# Un_Arduino.net
KiCad netlist of a schematic drawn in EAGLE
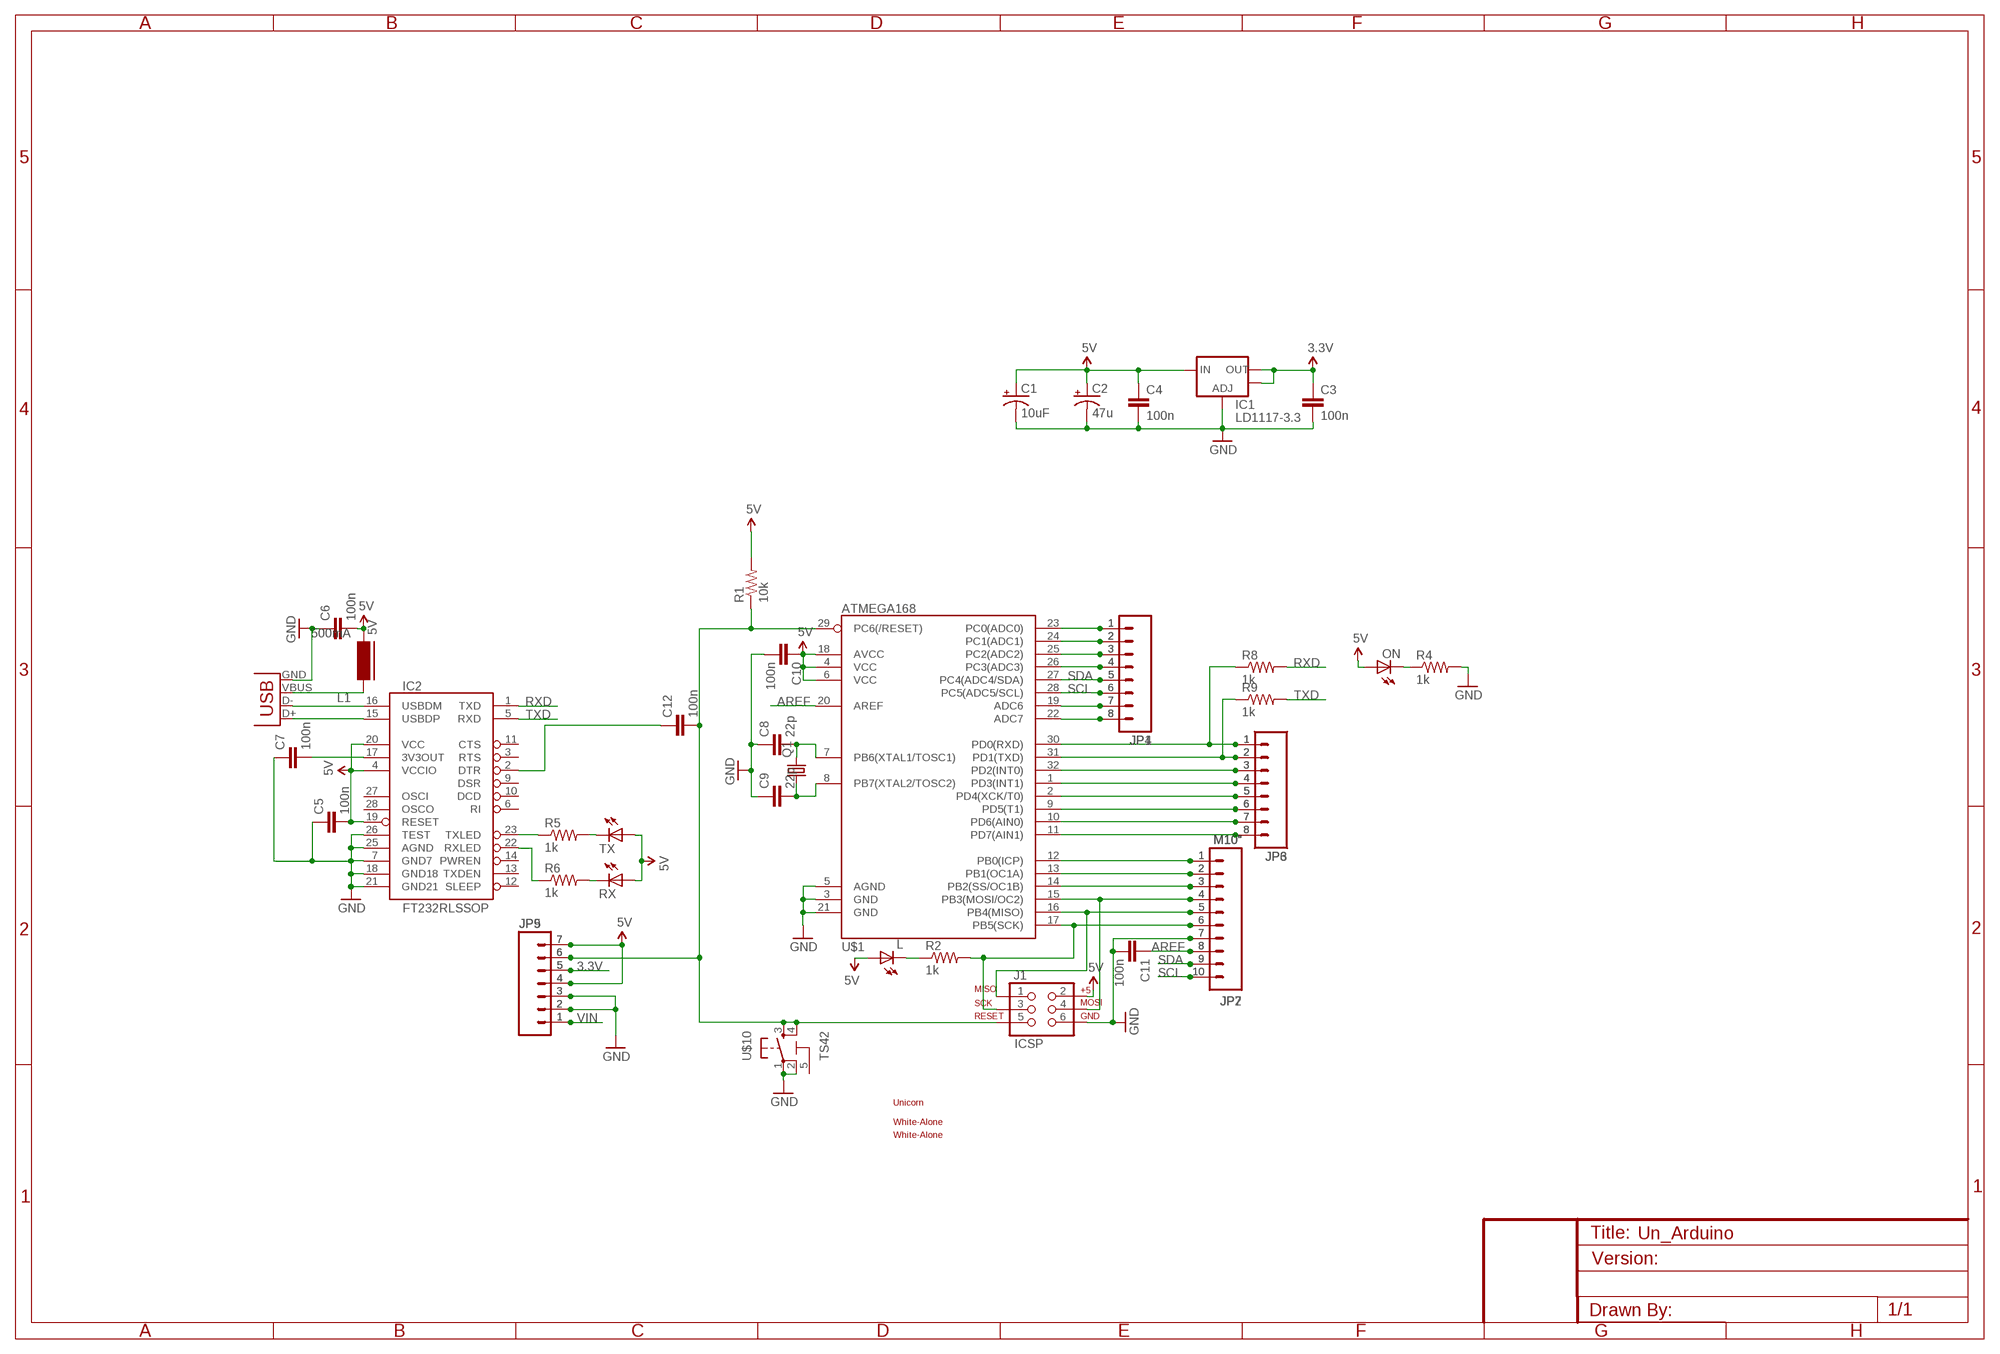
[diagram p0: schematic, sheet 1]

(export (version "E")
  (design (tool "Eeschema 10.0.6"))
  (components
    (comp (ref "C1")
      (value "10uF")
      (footprint "eagle-import:EIA3216")
      (libsource (lib "eagle-import") (part "CAP_POL1206"))
    )
    (comp (ref "C2")
      (value "47u")
      (footprint "eagle-import:PANASONIC_D")
      (libsource (lib "eagle-import") (part "CAP_POLD"))
    )
    (comp (ref "C3")
      (value "100n")
      (footprint "eagle-import:0603-CAP")
      (libsource (lib "eagle-import") (part "2SparkFun_CAP0603-CAP"))
    )
    (comp (ref "C4")
      (value "100n")
      (footprint "eagle-import:0603-CAP")
      (libsource (lib "eagle-import") (part "2SparkFun_CAP0603-CAP"))
    )
    (comp (ref "C5")
      (value "100n")
      (footprint "eagle-import:0603-CAP")
      (libsource (lib "eagle-import") (part "2SparkFun_CAP0603-CAP"))
    )
    (comp (ref "C6")
      (value "100n")
      (footprint "eagle-import:0603-CAP")
      (libsource (lib "eagle-import") (part "2SparkFun_CAP0603-CAP"))
    )
    (comp (ref "C7")
      (value "100n")
      (footprint "eagle-import:0603-CAP")
      (libsource (lib "eagle-import") (part "2SparkFun_CAP0603-CAP"))
    )
    (comp (ref "C8")
      (value "22p")
      (footprint "eagle-import:0603-CAP")
      (libsource (lib "eagle-import") (part "2SparkFun_CAP0603-CAP"))
    )
    (comp (ref "C9")
      (value "22p")
      (footprint "eagle-import:0603-CAP")
      (libsource (lib "eagle-import") (part "2SparkFun_CAP0603-CAP"))
    )
    (comp (ref "C10")
      (value "100n")
      (footprint "eagle-import:0603-CAP")
      (libsource (lib "eagle-import") (part "2SparkFun_CAP0603-CAP"))
    )
    (comp (ref "C11")
      (value "100n")
      (footprint "eagle-import:0603-CAP")
      (libsource (lib "eagle-import") (part "2SparkFun_CAP0603-CAP"))
    )
    (comp (ref "C12")
      (value "100n")
      (footprint "eagle-import:0603-CAP")
      (libsource (lib "eagle-import") (part "CAP0603-CAP"))
    )
    (comp (ref "IC1")
      (value "LD1117-3.3")
      (footprint "eagle-import:SOT223")
      (libsource (lib "eagle-import") (part "V_REG_LM1117SOT223"))
    )
    (comp (ref "IC2")
      (value "FT232RLSSOP")
      (footprint "eagle-import:SSOP28DB")
      (libsource (lib "eagle-import") (part "FT232RLSSOP"))
    )
    (comp (ref "J1")
      (value "ICSP")
      (footprint "eagle-import:2X3")
      (libsource (lib "eagle-import") (part "AVR_SPI_PRG_6PTH"))
    )
    (comp (ref "JP1")
      (value "M081X08")
      (footprint "eagle-import:1X08")
      (libsource (lib "eagle-import") (part "M081X08"))
    )
    (comp (ref "JP2")
      (value "M10\"")
      (footprint "eagle-import:1X10")
      (libsource (lib "eagle-import") (part "M10{dblquote}"))
    )
    (comp (ref "JP3")
      (value "M08")
      (footprint "eagle-import:1X08")
      (libsource (lib "eagle-import") (part "M08"))
    )
    (comp (ref "JP4")
      (value "M081X08")
      (footprint "eagle-import:1X08")
      (libsource (lib "eagle-import") (part "M081X08"))
    )
    (comp (ref "JP5")
      (value "M07")
      (footprint "eagle-import:1X07")
      (libsource (lib "eagle-import") (part "M07"))
    )
    (comp (ref "JP6")
      (value "M08")
      (footprint "eagle-import:1X08")
      (libsource (lib "eagle-import") (part "M08"))
    )
    (comp (ref "JP7")
      (value "M10\"")
      (footprint "eagle-import:1X10")
      (libsource (lib "eagle-import") (part "M10{dblquote}"))
    )
    (comp (ref "JP9")
      (value "M07")
      (footprint "eagle-import:1X07")
      (libsource (lib "eagle-import") (part "M07"))
    )
    (comp (ref "L")
      (value "LED0805")
      (footprint "eagle-import:LED-0805")
      (libsource (lib "eagle-import") (part "LED0805"))
    )
    (comp (ref "L1")
      (value "500mA")
      (footprint "eagle-import:FB805")
      (libsource (lib "eagle-import") (part "FERRITE-0805"))
    )
    (comp (ref "ON")
      (value "LED0805")
      (footprint "eagle-import:LED-0805")
      (libsource (lib "eagle-import") (part "LED0805"))
    )
    (comp (ref "Q1")
      (value "CRYSTALHC49US")
      (footprint "eagle-import:HC49US")
      (libsource (lib "eagle-import") (part "CRYSTALHC49US"))
    )
    (comp (ref "R1")
      (value "10k")
      (footprint "eagle-import:0603-RES")
      (libsource (lib "eagle-import") (part "RESISTOR0603-RES"))
    )
    (comp (ref "R2")
      (value "1k")
      (footprint "eagle-import:0603-RES")
      (libsource (lib "eagle-import") (part "RESISTOR0603-RES"))
    )
    (comp (ref "R4")
      (value "1k")
      (footprint "eagle-import:0603-RES")
      (libsource (lib "eagle-import") (part "RESISTOR0603-RES"))
    )
    (comp (ref "R5")
      (value "1k")
      (footprint "eagle-import:0603-RES")
      (libsource (lib "eagle-import") (part "RESISTOR0603-RES"))
    )
    (comp (ref "R6")
      (value "1k")
      (footprint "eagle-import:0603-RES")
      (libsource (lib "eagle-import") (part "RESISTOR0603-RES"))
    )
    (comp (ref "R8")
      (value "1k")
      (footprint "eagle-import:0603-RES")
      (libsource (lib "eagle-import") (part "RESISTOR0603-RES"))
    )
    (comp (ref "R9")
      (value "1k")
      (footprint "eagle-import:0603-RES")
      (libsource (lib "eagle-import") (part "RESISTOR0603-RES"))
    )
    (comp (ref "RX")
      (value "LED0805")
      (footprint "eagle-import:LED-0805")
      (libsource (lib "eagle-import") (part "LED0805"))
    )
    (comp (ref "TX")
      (value "LED0805")
      (footprint "eagle-import:LED-0805")
      (libsource (lib "eagle-import") (part "LED0805"))
    )
    (comp (ref "U$1")
      (value "ATMEGA168")
      (footprint "eagle-import:TQFP32-08")
      (libsource (lib "eagle-import") (part "ATMEGA168"))
    )
    (comp (ref "U$4")
      (value "UNICORN")
      (footprint "eagle-import:UNICORN_1")
      (libsource (lib "eagle-import") (part "UNICORN"))
    )
    (comp (ref "U$10")
      (value "TS42")
      (footprint "eagle-import:TS42")
      (libsource (lib "eagle-import") (part "TS42"))
    )
    (comp (ref "U$13")
      (value "WHITE-ALONE_0")
      (footprint "eagle-import:WHITE-ALONE_0")
      (libsource (lib "eagle-import") (part "WHITE-ALONE_0"))
    )
    (comp (ref "U$14")
      (value "WHITE-ALONE_0")
      (footprint "eagle-import:WHITE-ALONE_0")
      (libsource (lib "eagle-import") (part "WHITE-ALONE_0"))
    )
    (comp (ref "X1")
      (value "USBSMD")
      (footprint "eagle-import:USB-MINIB")
      (libsource (lib "eagle-import") (part "USBSMD"))
    )
  )
  (nets
    (net (code "1") (name "/AREF") (class "Default")
      (node (ref "C11") (pin "1") (pinfunction "1_1") (pintype "passive"))
      (node (ref "JP2") (pin "8") (pinfunction "8_8") (pintype "passive"))
      (node (ref "JP7") (pin "8") (pinfunction "8_8") (pintype "passive"))
      (node (ref "U$1") (pin "20") (pinfunction "AREF_20") (pintype "bidirectional"))
    )
    (net (code "2") (name "/RXD") (class "Default")
      (node (ref "IC2") (pin "1") (pinfunction "TXD_1") (pintype "output"))
      (node (ref "R8") (pin "2") (pinfunction "2_2") (pintype "passive"))
    )
    (net (code "3") (name "/SCL") (class "Default")
      (node (ref "JP1") (pin "6") (pinfunction "6_6") (pintype "passive"))
      (node (ref "JP2") (pin "10") (pinfunction "10_10") (pintype "passive"))
      (node (ref "JP4") (pin "6") (pinfunction "6_6") (pintype "passive"))
      (node (ref "JP7") (pin "10") (pinfunction "10_10") (pintype "passive"))
      (node (ref "U$1") (pin "28") (pinfunction "PC5(ADC5/SCL)_28") (pintype "bidirectional"))
    )
    (net (code "4") (name "/SDA") (class "Default")
      (node (ref "JP1") (pin "5") (pinfunction "5_5") (pintype "passive"))
      (node (ref "JP2") (pin "9") (pinfunction "9_9") (pintype "passive"))
      (node (ref "JP4") (pin "5") (pinfunction "5_5") (pintype "passive"))
      (node (ref "JP7") (pin "9") (pinfunction "9_9") (pintype "passive"))
      (node (ref "U$1") (pin "27") (pinfunction "PC4(ADC4/SDA)_27") (pintype "bidirectional"))
    )
    (net (code "5") (name "/TXD") (class "Default")
      (node (ref "IC2") (pin "5") (pinfunction "RXD_5") (pintype "input"))
      (node (ref "R9") (pin "2") (pinfunction "2_2") (pintype "passive"))
    )
    (net (code "6") (name "/VIN") (class "Default")
      (node (ref "JP5") (pin "1") (pinfunction "1_1") (pintype "passive"))
      (node (ref "JP9") (pin "1") (pinfunction "1_1") (pintype "passive"))
    )
    (net (code "7") (name "3.3V") (class "Default")
      (node (ref "C3") (pin "1") (pinfunction "1_1") (pintype "passive"))
      (node (ref "IC1") (pin "2") (pinfunction "OUT_2") (pintype "output"))
      (node (ref "IC1") (pin "4") (pinfunction "OUT_4") (pintype "output"))
      (node (ref "JP5") (pin "5") (pinfunction "5_5") (pintype "passive"))
      (node (ref "JP9") (pin "5") (pinfunction "5_5") (pintype "passive"))
    )
    (net (code "8") (name "5V") (class "Default")
      (node (ref "C1") (pin "A") (pinfunction "+_A") (pintype "passive"))
      (node (ref "C10") (pin "1") (pinfunction "1_1") (pintype "passive"))
      (node (ref "C2") (pin "+") (pinfunction "+_+") (pintype "passive"))
      (node (ref "C4") (pin "1") (pinfunction "1_1") (pintype "passive"))
      (node (ref "C5") (pin "2") (pinfunction "2_2") (pintype "passive"))
      (node (ref "C6") (pin "2") (pinfunction "2_2") (pintype "passive"))
      (node (ref "IC1") (pin "3") (pinfunction "IN_3") (pintype "input"))
      (node (ref "IC2") (pin "19") (pinfunction "RESET_19") (pintype "input"))
      (node (ref "IC2") (pin "20") (pinfunction "VCC_20") (pintype "power_in"))
      (node (ref "IC2") (pin "4") (pinfunction "VCCIO_4") (pintype "power_in"))
      (node (ref "J1") (pin "2") (pinfunction "2_2") (pintype "passive"))
      (node (ref "JP5") (pin "4") (pinfunction "4_4") (pintype "passive"))
      (node (ref "JP5") (pin "7") (pinfunction "7_7") (pintype "passive"))
      (node (ref "JP9") (pin "4") (pinfunction "4_4") (pintype "passive"))
      (node (ref "JP9") (pin "7") (pinfunction "7_7") (pintype "passive"))
      (node (ref "L") (pin "1") (pinfunction "A_1") (pintype "passive"))
      (node (ref "L1") (pin "2") (pinfunction "2_2") (pintype "passive"))
      (node (ref "ON") (pin "1") (pinfunction "A_1") (pintype "passive"))
      (node (ref "R1") (pin "2") (pinfunction "2_2") (pintype "passive"))
      (node (ref "RX") (pin "1") (pinfunction "A_1") (pintype "passive"))
      (node (ref "TX") (pin "1") (pinfunction "A_1") (pintype "passive"))
      (node (ref "U$1") (pin "18") (pinfunction "AVCC_18") (pintype "bidirectional"))
      (node (ref "U$1") (pin "4") (pinfunction "VCC_4") (pintype "bidirectional"))
      (node (ref "U$1") (pin "6") (pinfunction "VCC_6") (pintype "bidirectional"))
    )
    (net (code "9") (name "GND") (class "Default")
      (node (ref "C1") (pin "C") (pinfunction "-_C") (pintype "passive"))
      (node (ref "C10") (pin "2") (pinfunction "2_2") (pintype "passive"))
      (node (ref "C11") (pin "2") (pinfunction "2_2") (pintype "passive"))
      (node (ref "C2") (pin "-") (pinfunction "-_-") (pintype "passive"))
      (node (ref "C3") (pin "2") (pinfunction "2_2") (pintype "passive"))
      (node (ref "C4") (pin "2") (pinfunction "2_2") (pintype "passive"))
      (node (ref "C5") (pin "1") (pinfunction "1_1") (pintype "passive"))
      (node (ref "C6") (pin "1") (pinfunction "1_1") (pintype "passive"))
      (node (ref "C7") (pin "1") (pinfunction "1_1") (pintype "passive"))
      (node (ref "C8") (pin "1") (pinfunction "1_1") (pintype "passive"))
      (node (ref "C9") (pin "1") (pinfunction "1_1") (pintype "passive"))
      (node (ref "IC1") (pin "1") (pinfunction "ADJ_1") (pintype "input"))
      (node (ref "IC2") (pin "18") (pinfunction "GND18_18") (pintype "power_in"))
      (node (ref "IC2") (pin "21") (pinfunction "GND21_21") (pintype "power_in"))
      (node (ref "IC2") (pin "25") (pinfunction "AGND_25") (pintype "power_in"))
      (node (ref "IC2") (pin "26") (pinfunction "TEST_26") (pintype "input"))
      (node (ref "IC2") (pin "7") (pinfunction "GND7_7") (pintype "power_in"))
      (node (ref "J1") (pin "6") (pinfunction "6_6") (pintype "passive"))
      (node (ref "JP2") (pin "7") (pinfunction "7_7") (pintype "passive"))
      (node (ref "JP5") (pin "2") (pinfunction "2_2") (pintype "passive"))
      (node (ref "JP5") (pin "3") (pinfunction "3_3") (pintype "passive"))
      (node (ref "JP7") (pin "7") (pinfunction "7_7") (pintype "passive"))
      (node (ref "JP9") (pin "2") (pinfunction "2_2") (pintype "passive"))
      (node (ref "JP9") (pin "3") (pinfunction "3_3") (pintype "passive"))
      (node (ref "R4") (pin "2") (pinfunction "2_2") (pintype "passive"))
      (node (ref "U$1") (pin "21") (pinfunction "GND_21") (pintype "bidirectional"))
      (node (ref "U$1") (pin "3") (pinfunction "GND_3") (pintype "bidirectional"))
      (node (ref "U$1") (pin "5") (pinfunction "AGND_5") (pintype "bidirectional"))
      (node (ref "U$10") (pin "1") (pinfunction "1_1") (pintype "passive"))
      (node (ref "U$10") (pin "2") (pinfunction "2_2") (pintype "passive"))
      (node (ref "X1") (pin "GND") (pinfunction "GND_GND") (pintype "bidirectional"))
    )
    (net (code "10") (name "Net-(IC2-3V3OUT)") (class "Default")
      (node (ref "C7") (pin "2") (pinfunction "2_2") (pintype "passive"))
      (node (ref "IC2") (pin "17") (pinfunction "3V3OUT_17") (pintype "output"))
    )
    (net (code "11") (name "Net-(IC2-DTR)") (class "Default")
      (node (ref "C12") (pin "1") (pinfunction "1_1") (pintype "passive"))
      (node (ref "IC2") (pin "2") (pinfunction "DTR_2") (pintype "output"))
    )
    (net (code "12") (name "Net-(IC2-RXLED)") (class "Default")
      (node (ref "IC2") (pin "22") (pinfunction "RXLED_22") (pintype "input"))
      (node (ref "R6") (pin "1") (pinfunction "1_1") (pintype "passive"))
    )
    (net (code "13") (name "Net-(IC2-TXLED)") (class "Default")
      (node (ref "IC2") (pin "23") (pinfunction "TXLED_23") (pintype "input"))
      (node (ref "R5") (pin "1") (pinfunction "1_1") (pintype "passive"))
    )
    (net (code "14") (name "Net-(IC2-USBDM)") (class "Default")
      (node (ref "IC2") (pin "16") (pinfunction "USBDM_16") (pintype "bidirectional"))
      (node (ref "X1") (pin "D-") (pinfunction "D-_D-") (pintype "bidirectional"))
    )
    (net (code "15") (name "Net-(IC2-USBDP)") (class "Default")
      (node (ref "IC2") (pin "15") (pinfunction "USBDP_15") (pintype "bidirectional"))
      (node (ref "X1") (pin "D+") (pinfunction "D+_D+") (pintype "bidirectional"))
    )
    (net (code "16") (name "Net-(L-C)") (class "Default")
      (node (ref "L") (pin "2") (pinfunction "C_2") (pintype "passive"))
      (node (ref "R2") (pin "1") (pinfunction "1_1") (pintype "passive"))
    )
    (net (code "17") (name "Net-(L1-Pad1)") (class "Default")
      (node (ref "L1") (pin "1") (pinfunction "1_1") (pintype "passive"))
      (node (ref "X1") (pin "VBUS") (pinfunction "VBUS_VBUS") (pintype "bidirectional"))
    )
    (net (code "18") (name "Net-(ON-C)") (class "Default")
      (node (ref "ON") (pin "2") (pinfunction "C_2") (pintype "passive"))
      (node (ref "R4") (pin "1") (pinfunction "1_1") (pintype "passive"))
    )
    (net (code "19") (name "Net-(RX-C)") (class "Default")
      (node (ref "R6") (pin "2") (pinfunction "2_2") (pintype "passive"))
      (node (ref "RX") (pin "2") (pinfunction "C_2") (pintype "passive"))
    )
    (net (code "20") (name "Net-(TX-C)") (class "Default")
      (node (ref "R5") (pin "2") (pinfunction "2_2") (pintype "passive"))
      (node (ref "TX") (pin "2") (pinfunction "C_2") (pintype "passive"))
    )
    (net (code "21") (name "Net-(U$1-ADC6)") (class "Default")
      (node (ref "JP1") (pin "7") (pinfunction "7_7") (pintype "passive"))
      (node (ref "JP4") (pin "7") (pinfunction "7_7") (pintype "passive"))
      (node (ref "U$1") (pin "19") (pinfunction "ADC6_19") (pintype "bidirectional"))
    )
    (net (code "22") (name "Net-(U$1-ADC7)") (class "Default")
      (node (ref "JP1") (pin "8") (pinfunction "8_8") (pintype "passive"))
      (node (ref "JP4") (pin "8") (pinfunction "8_8") (pintype "passive"))
      (node (ref "U$1") (pin "22") (pinfunction "ADC7_22") (pintype "bidirectional"))
    )
    (net (code "23") (name "Net-(U$1-PB0(ICP))") (class "Default")
      (node (ref "JP2") (pin "1") (pinfunction "1_1") (pintype "passive"))
      (node (ref "JP7") (pin "1") (pinfunction "1_1") (pintype "passive"))
      (node (ref "U$1") (pin "12") (pinfunction "PB0(ICP)_12") (pintype "bidirectional"))
    )
    (net (code "24") (name "Net-(U$1-PB1(OC1A))") (class "Default")
      (node (ref "JP2") (pin "2") (pinfunction "2_2") (pintype "passive"))
      (node (ref "JP7") (pin "2") (pinfunction "2_2") (pintype "passive"))
      (node (ref "U$1") (pin "13") (pinfunction "PB1(OC1A)_13") (pintype "bidirectional"))
    )
    (net (code "25") (name "Net-(U$1-PB2(SS{slash}OC1B))") (class "Default")
      (node (ref "JP2") (pin "3") (pinfunction "3_3") (pintype "passive"))
      (node (ref "JP7") (pin "3") (pinfunction "3_3") (pintype "passive"))
      (node (ref "U$1") (pin "14") (pinfunction "PB2(SS/OC1B)_14") (pintype "bidirectional"))
    )
    (net (code "26") (name "Net-(U$1-PB3(MOSI{slash}OC2))") (class "Default")
      (node (ref "J1") (pin "4") (pinfunction "4_4") (pintype "passive"))
      (node (ref "JP2") (pin "4") (pinfunction "4_4") (pintype "passive"))
      (node (ref "JP7") (pin "4") (pinfunction "4_4") (pintype "passive"))
      (node (ref "U$1") (pin "15") (pinfunction "PB3(MOSI/OC2)_15") (pintype "bidirectional"))
    )
    (net (code "27") (name "Net-(U$1-PB4(MISO))") (class "Default")
      (node (ref "J1") (pin "1") (pinfunction "1_1") (pintype "passive"))
      (node (ref "JP2") (pin "5") (pinfunction "5_5") (pintype "passive"))
      (node (ref "JP7") (pin "5") (pinfunction "5_5") (pintype "passive"))
      (node (ref "U$1") (pin "16") (pinfunction "PB4(MISO)_16") (pintype "bidirectional"))
    )
    (net (code "28") (name "Net-(U$1-PB5(SCK))") (class "Default")
      (node (ref "J1") (pin "3") (pinfunction "3_3") (pintype "passive"))
      (node (ref "JP2") (pin "6") (pinfunction "6_6") (pintype "passive"))
      (node (ref "JP7") (pin "6") (pinfunction "6_6") (pintype "passive"))
      (node (ref "R2") (pin "2") (pinfunction "2_2") (pintype "passive"))
      (node (ref "U$1") (pin "17") (pinfunction "PB5(SCK)_17") (pintype "bidirectional"))
    )
    (net (code "29") (name "Net-(U$1-PB6(XTAL1{slash}TOSC1))") (class "Default")
      (node (ref "C8") (pin "2") (pinfunction "2_2") (pintype "passive"))
      (node (ref "Q1") (pin "2") (pinfunction "2_2") (pintype "passive"))
      (node (ref "U$1") (pin "7") (pinfunction "PB6(XTAL1/TOSC1)_7") (pintype "bidirectional"))
    )
    (net (code "30") (name "Net-(U$1-PB7(XTAL2{slash}TOSC2))") (class "Default")
      (node (ref "C9") (pin "2") (pinfunction "2_2") (pintype "passive"))
      (node (ref "Q1") (pin "1") (pinfunction "1_1") (pintype "passive"))
      (node (ref "U$1") (pin "8") (pinfunction "PB7(XTAL2/TOSC2)_8") (pintype "bidirectional"))
    )
    (net (code "31") (name "Net-(U$1-PC0(ADC0))") (class "Default")
      (node (ref "JP1") (pin "1") (pinfunction "1_1") (pintype "passive"))
      (node (ref "JP4") (pin "1") (pinfunction "1_1") (pintype "passive"))
      (node (ref "U$1") (pin "23") (pinfunction "PC0(ADC0)_23") (pintype "bidirectional"))
    )
    (net (code "32") (name "Net-(U$1-PC1(ADC1))") (class "Default")
      (node (ref "JP1") (pin "2") (pinfunction "2_2") (pintype "passive"))
      (node (ref "JP4") (pin "2") (pinfunction "2_2") (pintype "passive"))
      (node (ref "U$1") (pin "24") (pinfunction "PC1(ADC1)_24") (pintype "bidirectional"))
    )
    (net (code "33") (name "Net-(U$1-PC2(ADC2))") (class "Default")
      (node (ref "JP1") (pin "3") (pinfunction "3_3") (pintype "passive"))
      (node (ref "JP4") (pin "3") (pinfunction "3_3") (pintype "passive"))
      (node (ref "U$1") (pin "25") (pinfunction "PC2(ADC2)_25") (pintype "bidirectional"))
    )
    (net (code "34") (name "Net-(U$1-PC3(ADC3))") (class "Default")
      (node (ref "JP1") (pin "4") (pinfunction "4_4") (pintype "passive"))
      (node (ref "JP4") (pin "4") (pinfunction "4_4") (pintype "passive"))
      (node (ref "U$1") (pin "26") (pinfunction "PC3(ADC3)_26") (pintype "bidirectional"))
    )
    (net (code "35") (name "Net-(U$1-PC6({slash}RESET))") (class "Default")
      (node (ref "C12") (pin "2") (pinfunction "2_2") (pintype "passive"))
      (node (ref "J1") (pin "5") (pinfunction "5_5") (pintype "passive"))
      (node (ref "JP5") (pin "6") (pinfunction "6_6") (pintype "passive"))
      (node (ref "JP9") (pin "6") (pinfunction "6_6") (pintype "passive"))
      (node (ref "R1") (pin "1") (pinfunction "1_1") (pintype "passive"))
      (node (ref "U$1") (pin "29") (pinfunction "PC6(/RESET)_29") (pintype "bidirectional"))
      (node (ref "U$10") (pin "3") (pinfunction "3_3") (pintype "passive"))
      (node (ref "U$10") (pin "4") (pinfunction "4_4") (pintype "passive"))
    )
    (net (code "36") (name "Net-(U$1-PD0(RXD))") (class "Default")
      (node (ref "JP3") (pin "1") (pinfunction "1_1") (pintype "passive"))
      (node (ref "JP6") (pin "1") (pinfunction "1_1") (pintype "passive"))
      (node (ref "R8") (pin "1") (pinfunction "1_1") (pintype "passive"))
      (node (ref "U$1") (pin "30") (pinfunction "PD0(RXD)_30") (pintype "bidirectional"))
    )
    (net (code "37") (name "Net-(U$1-PD1(TXD))") (class "Default")
      (node (ref "JP3") (pin "2") (pinfunction "2_2") (pintype "passive"))
      (node (ref "JP6") (pin "2") (pinfunction "2_2") (pintype "passive"))
      (node (ref "R9") (pin "1") (pinfunction "1_1") (pintype "passive"))
      (node (ref "U$1") (pin "31") (pinfunction "PD1(TXD)_31") (pintype "bidirectional"))
    )
    (net (code "38") (name "Net-(U$1-PD2(INT0))") (class "Default")
      (node (ref "JP3") (pin "3") (pinfunction "3_3") (pintype "passive"))
      (node (ref "JP6") (pin "3") (pinfunction "3_3") (pintype "passive"))
      (node (ref "U$1") (pin "32") (pinfunction "PD2(INT0)_32") (pintype "bidirectional"))
    )
    (net (code "39") (name "Net-(U$1-PD3(INT1))") (class "Default")
      (node (ref "JP3") (pin "4") (pinfunction "4_4") (pintype "passive"))
      (node (ref "JP6") (pin "4") (pinfunction "4_4") (pintype "passive"))
      (node (ref "U$1") (pin "1") (pinfunction "PD3(INT1)_1") (pintype "bidirectional"))
    )
    (net (code "40") (name "Net-(U$1-PD4(XCK{slash}T0))") (class "Default")
      (node (ref "JP3") (pin "5") (pinfunction "5_5") (pintype "passive"))
      (node (ref "JP6") (pin "5") (pinfunction "5_5") (pintype "passive"))
      (node (ref "U$1") (pin "2") (pinfunction "PD4(XCK/T0)_2") (pintype "bidirectional"))
    )
    (net (code "41") (name "Net-(U$1-PD5(T1))") (class "Default")
      (node (ref "JP3") (pin "6") (pinfunction "6_6") (pintype "passive"))
      (node (ref "JP6") (pin "6") (pinfunction "6_6") (pintype "passive"))
      (node (ref "U$1") (pin "9") (pinfunction "PD5(T1)_9") (pintype "bidirectional"))
    )
    (net (code "42") (name "Net-(U$1-PD6(AIN0))") (class "Default")
      (node (ref "JP3") (pin "7") (pinfunction "7_7") (pintype "passive"))
      (node (ref "JP6") (pin "7") (pinfunction "7_7") (pintype "passive"))
      (node (ref "U$1") (pin "10") (pinfunction "PD6(AIN0)_10") (pintype "bidirectional"))
    )
    (net (code "43") (name "Net-(U$1-PD7(AIN1))") (class "Default")
      (node (ref "JP3") (pin "8") (pinfunction "8_8") (pintype "passive"))
      (node (ref "JP6") (pin "8") (pinfunction "8_8") (pintype "passive"))
      (node (ref "U$1") (pin "11") (pinfunction "PD7(AIN1)_11") (pintype "bidirectional"))
    )
    (net (code "44") (name "unconnected-(IC2-CTS-Pad11)") (class "Default")
      (node (ref "IC2") (pin "11") (pinfunction "CTS_11") (pintype "input"))
    )
    (net (code "45") (name "unconnected-(IC2-DCD-Pad10)") (class "Default")
      (node (ref "IC2") (pin "10") (pinfunction "DCD_10") (pintype "input"))
    )
    (net (code "46") (name "unconnected-(IC2-DSR-Pad9)") (class "Default")
      (node (ref "IC2") (pin "9") (pinfunction "DSR_9") (pintype "input"))
    )
    (net (code "47") (name "unconnected-(IC2-OSCI-Pad27)") (class "Default")
      (node (ref "IC2") (pin "27") (pinfunction "OSCI_27") (pintype "input"))
    )
    (net (code "48") (name "unconnected-(IC2-OSCO-Pad28)") (class "Default")
      (node (ref "IC2") (pin "28") (pinfunction "OSCO_28") (pintype "output"))
    )
    (net (code "49") (name "unconnected-(IC2-PWREN-Pad14)") (class "Default")
      (node (ref "IC2") (pin "14") (pinfunction "PWREN_14") (pintype "input"))
    )
    (net (code "50") (name "unconnected-(IC2-RI-Pad6)") (class "Default")
      (node (ref "IC2") (pin "6") (pinfunction "RI_6") (pintype "input"))
    )
    (net (code "51") (name "unconnected-(IC2-RTS-Pad3)") (class "Default")
      (node (ref "IC2") (pin "3") (pinfunction "RTS_3") (pintype "output"))
    )
    (net (code "52") (name "unconnected-(IC2-SLEEP-Pad12)") (class "Default")
      (node (ref "IC2") (pin "12") (pinfunction "SLEEP_12") (pintype "input"))
    )
    (net (code "53") (name "unconnected-(IC2-TXDEN-Pad13)") (class "Default")
      (node (ref "IC2") (pin "13") (pinfunction "TXDEN_13") (pintype "input"))
    )
    (net (code "54") (name "unconnected-(U$10-Pad5)") (class "Default")
      (node (ref "U$10") (pin "5") (pinfunction "5_5") (pintype "passive"))
    )
  )
)
